# board.net
KiCad netlist of a schematic drawn in EAGLE
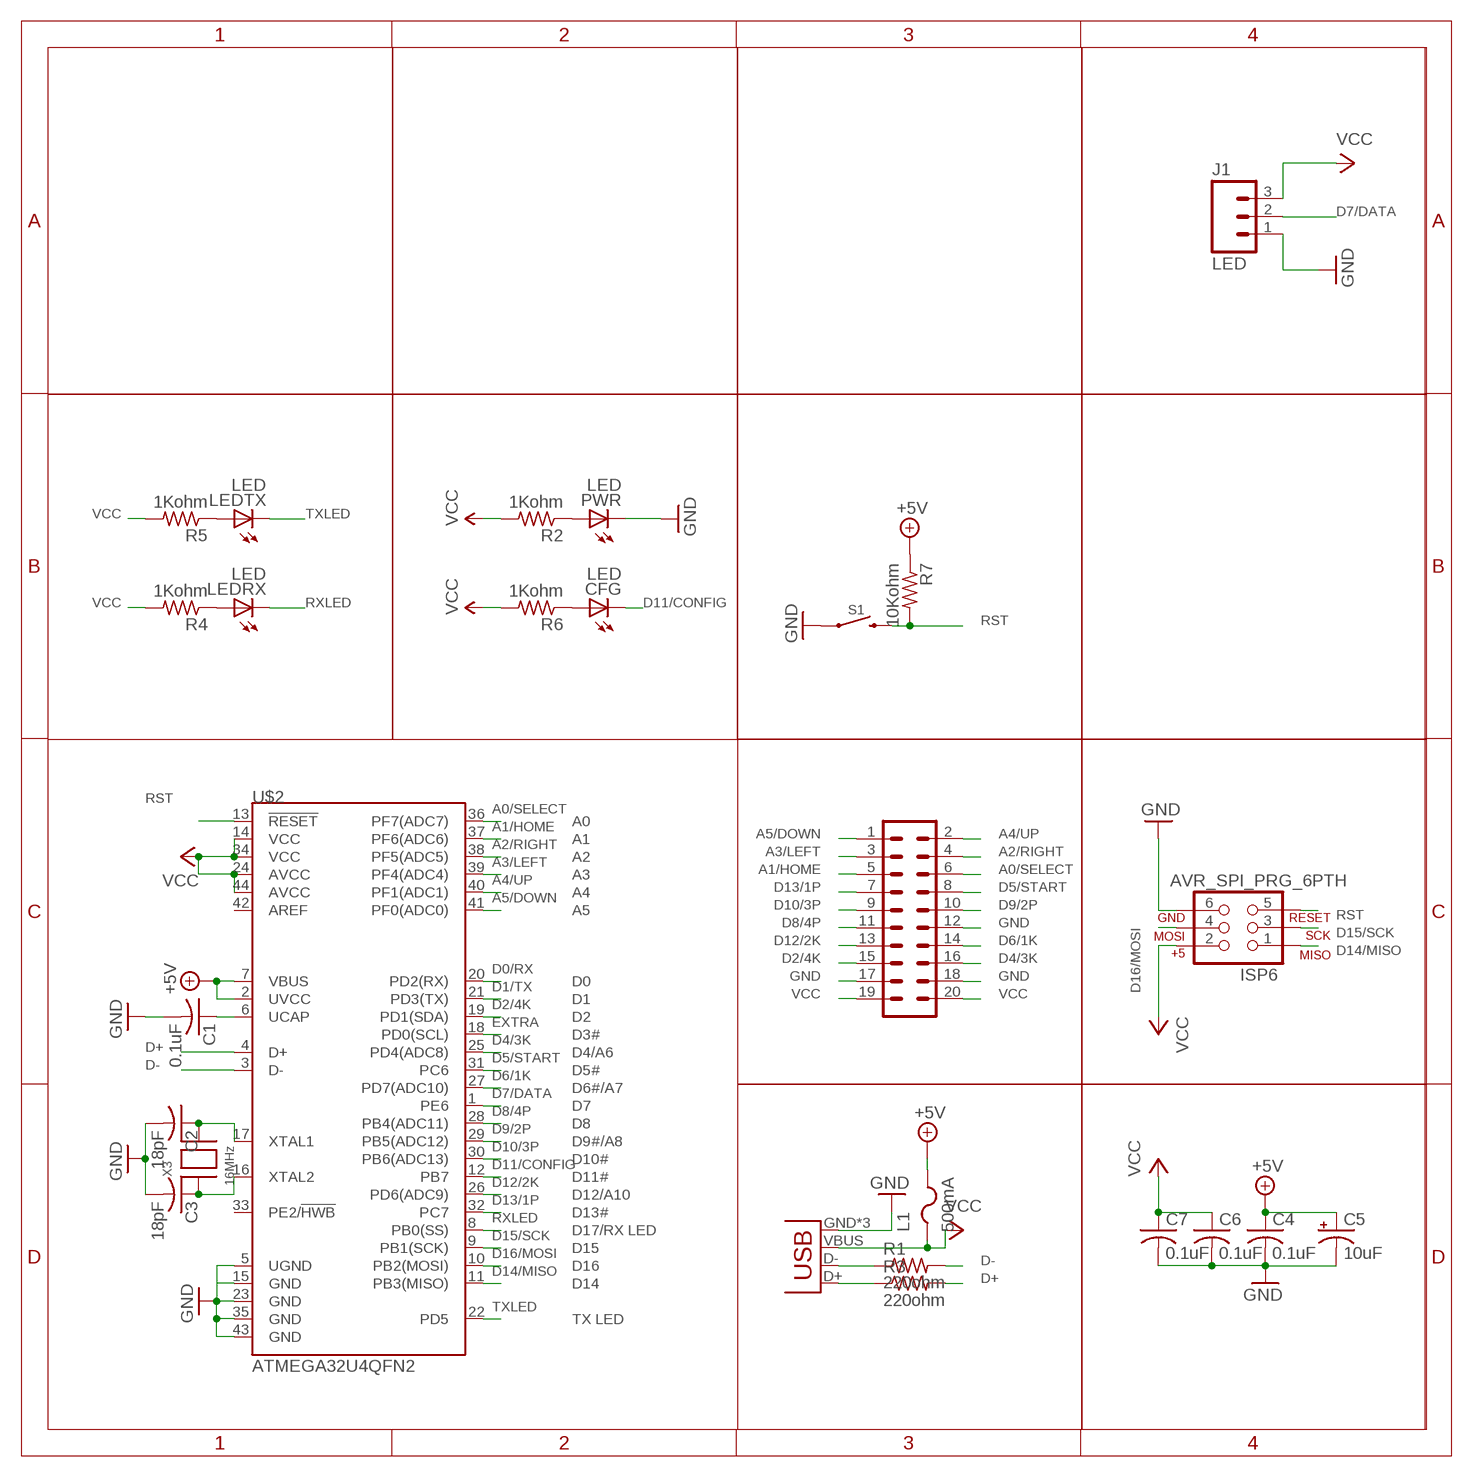
[diagram p0: schematic, sheet 1]

(export (version "E")
  (design (tool "Eeschema 10.0.6"))
  (components
    (comp (ref "C1")
      (value "0.1uF")
      (footprint "eagle-import:C0603")
      (libsource (lib "eagle-import") (part "C-USC0603"))
    )
    (comp (ref "C2")
      (value "18pF")
      (footprint "eagle-import:C0603")
      (libsource (lib "eagle-import") (part "C-USC0603"))
    )
    (comp (ref "C3")
      (value "18pF")
      (footprint "eagle-import:C0603")
      (libsource (lib "eagle-import") (part "C-USC0603"))
    )
    (comp (ref "C4")
      (value "0.1uF")
      (footprint "eagle-import:C0603")
      (libsource (lib "eagle-import") (part "C-USC0603"))
    )
    (comp (ref "C5")
      (value "10uF")
      (footprint "eagle-import:0603-POLAR")
      (libsource (lib "eagle-import") (part "10UF-POLAR-0603-6.3V-20%(TANT)"))
    )
    (comp (ref "C6")
      (value "0.1uF")
      (footprint "eagle-import:C0603")
      (libsource (lib "eagle-import") (part "C-USC0603"))
    )
    (comp (ref "C7")
      (value "0.1uF")
      (footprint "eagle-import:C0603")
      (libsource (lib "eagle-import") (part "C-USC0603"))
    )
    (comp (ref "CFG")
      (value "LED")
      (footprint "eagle-import:CHIPLED_0603")
      (libsource (lib "eagle-import") (part "LEDCHIPLED_0603"))
    )
    (comp (ref "CN1")
      (value "USB-MICROB")
      (footprint "eagle-import:USB-MICROB")
      (libsource (lib "eagle-import") (part "USB-MICROB"))
    )
    (comp (ref "ISP6")
      (value "AVR_SPI_PRG_6PTH")
      (footprint "eagle-import:2X3")
      (libsource (lib "eagle-import") (part "AVR_SPI_PRG_6PTH"))
    )
    (comp (ref "J1")
      (value "LED")
      (footprint "eagle-import:JST-3-PTH-VERT")
      (libsource (lib "eagle-import") (part "M03JST-PTH-VERT"))
    )
    (comp (ref "L1")
      (value "500mA")
      (footprint "eagle-import:R1206")
      (libsource (lib "eagle-import") (part "PTCFUSE-1206"))
    )
    (comp (ref "LEDRX")
      (value "LED")
      (footprint "eagle-import:CHIPLED_0603")
      (libsource (lib "eagle-import") (part "LEDCHIPLED_0603"))
    )
    (comp (ref "LEDTX")
      (value "LED")
      (footprint "eagle-import:CHIPLED_0603")
      (libsource (lib "eagle-import") (part "LEDCHIPLED_0603"))
    )
    (comp (ref "PWR")
      (value "LED")
      (footprint "eagle-import:CHIPLED_0603")
      (libsource (lib "eagle-import") (part "LEDCHIPLED_0603"))
    )
    (comp (ref "R1")
      (value "220ohm")
      (footprint "eagle-import:R0603")
      (libsource (lib "eagle-import") (part "R-US_R0603"))
    )
    (comp (ref "R2")
      (value "1Kohm")
      (footprint "eagle-import:R0603")
      (libsource (lib "eagle-import") (part "R-US_R0603"))
    )
    (comp (ref "R3")
      (value "220ohm")
      (footprint "eagle-import:R0603")
      (libsource (lib "eagle-import") (part "R-US_R0603"))
    )
    (comp (ref "R4")
      (value "1Kohm")
      (footprint "eagle-import:R0603")
      (libsource (lib "eagle-import") (part "R-US_R0603"))
    )
    (comp (ref "R5")
      (value "1Kohm")
      (footprint "eagle-import:R0603")
      (libsource (lib "eagle-import") (part "R-US_R0603"))
    )
    (comp (ref "R6")
      (value "1Kohm")
      (footprint "eagle-import:R0603")
      (libsource (lib "eagle-import") (part "R-US_R0603"))
    )
    (comp (ref "R7")
      (value "10Kohm")
      (footprint "eagle-import:R0603")
      (libsource (lib "eagle-import") (part "R-US_R0603"))
    )
    (comp (ref "S1")
      (value "MOMENTARY-SWITCH-SPST-SMD-4.6X2.8MM")
      (footprint "eagle-import:TACTILE_SWITCH_SMD_4.6X2.8MM")
      (libsource (lib "eagle-import") (part "MOMENTARY-SWITCH-SPST-SMD-4.6X2.8MM"))
    )
    (comp (ref "U$1")
      (value "M10X2")
      (footprint "eagle-import:2X10")
      (libsource (lib "eagle-import") (part "M10X2"))
    )
    (comp (ref "U$2")
      (value "ATMEGA32U4QFN2")
      (footprint "eagle-import:SPARKFUN-DIGITALIC_QFN-44-NOPAD")
      (libsource (lib "eagle-import") (part "ATMEGA32U4QFN2"))
    )
    (comp (ref "X3")
      (value "16MHz")
      (footprint "eagle-import:NX5032")
      (libsource (lib "eagle-import") (part "XTALNX5032"))
    )
  )
  (nets
    (net (code "1") (name "+5V") (class "Default")
      (node (ref "C4") (pin "1") (pinfunction "1_1") (pintype "passive"))
      (node (ref "C5") (pin "+") (pinfunction "+_+") (pintype "passive"))
      (node (ref "L1") (pin "2") (pinfunction "2_2") (pintype "passive"))
      (node (ref "R7") (pin "1") (pinfunction "1_1") (pintype "passive"))
      (node (ref "U$2") (pin "2") (pinfunction "UVCC_2") (pintype "bidirectional"))
      (node (ref "U$2") (pin "7") (pinfunction "VBUS_7") (pintype "bidirectional"))
    )
    (net (code "2") (name "/A0{slash}SELECT") (class "Default")
      (node (ref "U$1") (pin "6") (pinfunction "6_6") (pintype "passive"))
      (node (ref "U$2") (pin "36") (pinfunction "PF7(ADC7)_36") (pintype "bidirectional"))
    )
    (net (code "3") (name "/A1{slash}HOME") (class "Default")
      (node (ref "U$1") (pin "5") (pinfunction "5_5") (pintype "passive"))
      (node (ref "U$2") (pin "37") (pinfunction "PF6(ADC6)_37") (pintype "bidirectional"))
    )
    (net (code "4") (name "/A2{slash}RIGHT") (class "Default")
      (node (ref "U$1") (pin "4") (pinfunction "4_4") (pintype "passive"))
      (node (ref "U$2") (pin "38") (pinfunction "PF5(ADC5)_38") (pintype "bidirectional"))
    )
    (net (code "5") (name "/A3{slash}LEFT") (class "Default")
      (node (ref "U$1") (pin "3") (pinfunction "3_3") (pintype "passive"))
      (node (ref "U$2") (pin "39") (pinfunction "PF4(ADC4)_39") (pintype "bidirectional"))
    )
    (net (code "6") (name "/A4{slash}UP") (class "Default")
      (node (ref "U$1") (pin "2") (pinfunction "2_2") (pintype "passive"))
      (node (ref "U$2") (pin "40") (pinfunction "PF1(ADC1)_40") (pintype "bidirectional"))
    )
    (net (code "7") (name "/A5{slash}DOWN") (class "Default")
      (node (ref "U$1") (pin "1") (pinfunction "1_1") (pintype "passive"))
      (node (ref "U$2") (pin "41") (pinfunction "PF0(ADC0)_41") (pintype "bidirectional"))
    )
    (net (code "8") (name "/D+") (class "Default")
      (node (ref "R3") (pin "2") (pinfunction "2_2") (pintype "passive"))
      (node (ref "U$2") (pin "4") (pinfunction "D+_4") (pintype "bidirectional"))
    )
    (net (code "9") (name "/D-") (class "Default")
      (node (ref "R1") (pin "2") (pinfunction "2_2") (pintype "passive"))
      (node (ref "U$2") (pin "3") (pinfunction "D-_3") (pintype "bidirectional"))
    )
    (net (code "10") (name "/D0{slash}RX") (class "Default")
      (node (ref "U$2") (pin "20") (pinfunction "PD2(RX)_20") (pintype "bidirectional"))
    )
    (net (code "11") (name "/D1{slash}TX") (class "Default")
      (node (ref "U$2") (pin "21") (pinfunction "PD3(TX)_21") (pintype "bidirectional"))
    )
    (net (code "12") (name "/D2{slash}4K") (class "Default")
      (node (ref "U$1") (pin "15") (pinfunction "15_15") (pintype "passive"))
      (node (ref "U$2") (pin "19") (pinfunction "PD1(SDA)_19") (pintype "bidirectional"))
    )
    (net (code "13") (name "/D4{slash}3K") (class "Default")
      (node (ref "U$1") (pin "16") (pinfunction "16_16") (pintype "passive"))
      (node (ref "U$2") (pin "25") (pinfunction "PD4(ADC8)_25") (pintype "bidirectional"))
    )
    (net (code "14") (name "/D5{slash}START") (class "Default")
      (node (ref "U$1") (pin "8") (pinfunction "8_8") (pintype "passive"))
      (node (ref "U$2") (pin "31") (pinfunction "PC6_31") (pintype "bidirectional"))
    )
    (net (code "15") (name "/D6{slash}1K") (class "Default")
      (node (ref "U$1") (pin "14") (pinfunction "14_14") (pintype "passive"))
      (node (ref "U$2") (pin "27") (pinfunction "PD7(ADC10)_27") (pintype "bidirectional"))
    )
    (net (code "16") (name "/D7{slash}DATA") (class "Default")
      (node (ref "J1") (pin "2") (pinfunction "2_2") (pintype "passive"))
      (node (ref "U$2") (pin "1") (pinfunction "PE6_1") (pintype "bidirectional"))
    )
    (net (code "17") (name "/D8{slash}4P") (class "Default")
      (node (ref "U$1") (pin "11") (pinfunction "11_11") (pintype "passive"))
      (node (ref "U$2") (pin "28") (pinfunction "PB4(ADC11)_28") (pintype "bidirectional"))
    )
    (net (code "18") (name "/D9{slash}2P") (class "Default")
      (node (ref "U$1") (pin "10") (pinfunction "10_10") (pintype "passive"))
      (node (ref "U$2") (pin "29") (pinfunction "PB5(ADC12)_29") (pintype "bidirectional"))
    )
    (net (code "19") (name "/D10{slash}3P") (class "Default")
      (node (ref "U$1") (pin "9") (pinfunction "9_9") (pintype "passive"))
      (node (ref "U$2") (pin "30") (pinfunction "PB6(ADC13)_30") (pintype "bidirectional"))
    )
    (net (code "20") (name "/D11{slash}CONFIG") (class "Default")
      (node (ref "CFG") (pin "C") (pinfunction "C_C") (pintype "passive"))
      (node (ref "U$2") (pin "12") (pinfunction "PB7_12") (pintype "bidirectional"))
    )
    (net (code "21") (name "/D12{slash}2K") (class "Default")
      (node (ref "U$1") (pin "13") (pinfunction "13_13") (pintype "passive"))
      (node (ref "U$2") (pin "26") (pinfunction "PD6(ADC9)_26") (pintype "bidirectional"))
    )
    (net (code "22") (name "/D13{slash}1P") (class "Default")
      (node (ref "U$1") (pin "7") (pinfunction "7_7") (pintype "passive"))
      (node (ref "U$2") (pin "32") (pinfunction "PC7_32") (pintype "bidirectional"))
    )
    (net (code "23") (name "/D14{slash}MISO") (class "Default")
      (node (ref "ISP6") (pin "1") (pinfunction "1_1") (pintype "passive"))
      (node (ref "U$2") (pin "11") (pinfunction "PB3(MISO)_11") (pintype "bidirectional"))
    )
    (net (code "24") (name "/D15{slash}SCK") (class "Default")
      (node (ref "ISP6") (pin "3") (pinfunction "3_3") (pintype "passive"))
      (node (ref "U$2") (pin "9") (pinfunction "PB1(SCK)_9") (pintype "bidirectional"))
    )
    (net (code "25") (name "/D16{slash}MOSI") (class "Default")
      (node (ref "ISP6") (pin "4") (pinfunction "4_4") (pintype "passive"))
      (node (ref "U$2") (pin "10") (pinfunction "PB2(MOSI)_10") (pintype "bidirectional"))
    )
    (net (code "26") (name "/EXTRA") (class "Default")
      (node (ref "U$2") (pin "18") (pinfunction "PD0(SCL)_18") (pintype "bidirectional"))
    )
    (net (code "27") (name "/RST") (class "Default")
      (node (ref "ISP6") (pin "5") (pinfunction "5_5") (pintype "passive"))
      (node (ref "R7") (pin "2") (pinfunction "2_2") (pintype "passive"))
      (node (ref "S1") (pin "3") (pinfunction "2_3") (pintype "passive"))
      (node (ref "S1") (pin "4") (pinfunction "2_4") (pintype "passive"))
      (node (ref "U$2") (pin "13") (pinfunction "~{RESET}_13") (pintype "bidirectional"))
    )
    (net (code "28") (name "/RXLED") (class "Default")
      (node (ref "LEDRX") (pin "C") (pinfunction "C_C") (pintype "passive"))
      (node (ref "U$2") (pin "8") (pinfunction "PB0(SS)_8") (pintype "bidirectional"))
    )
    (net (code "29") (name "/TXLED") (class "Default")
      (node (ref "LEDTX") (pin "C") (pinfunction "C_C") (pintype "passive"))
      (node (ref "U$2") (pin "22") (pinfunction "PD5_22") (pintype "bidirectional"))
    )
    (net (code "30") (name "GND") (class "Default")
      (node (ref "C1") (pin "2") (pinfunction "2_2") (pintype "passive"))
      (node (ref "C2") (pin "2") (pinfunction "2_2") (pintype "passive"))
      (node (ref "C3") (pin "2") (pinfunction "2_2") (pintype "passive"))
      (node (ref "C4") (pin "2") (pinfunction "2_2") (pintype "passive"))
      (node (ref "C5") (pin "-") (pinfunction "-_-") (pintype "passive"))
      (node (ref "C6") (pin "2") (pinfunction "2_2") (pintype "passive"))
      (node (ref "C7") (pin "2") (pinfunction "2_2") (pintype "passive"))
      (node (ref "CN1") (pin "GND") (pinfunction "GND_GND") (pintype "bidirectional"))
      (node (ref "CN1") (pin "MT1") (pinfunction "GND_MT1") (pintype "bidirectional"))
      (node (ref "CN1") (pin "MT2") (pinfunction "GND_MT2") (pintype "bidirectional"))
      (node (ref "ISP6") (pin "6") (pinfunction "6_6") (pintype "passive"))
      (node (ref "J1") (pin "1") (pinfunction "1_1") (pintype "passive"))
      (node (ref "PWR") (pin "C") (pinfunction "C_C") (pintype "passive"))
      (node (ref "S1") (pin "1") (pinfunction "1_1") (pintype "passive"))
      (node (ref "S1") (pin "2") (pinfunction "1_2") (pintype "passive"))
      (node (ref "U$1") (pin "12") (pinfunction "12_12") (pintype "passive"))
      (node (ref "U$1") (pin "17") (pinfunction "17_17") (pintype "passive"))
      (node (ref "U$1") (pin "18") (pinfunction "18_18") (pintype "passive"))
      (node (ref "U$2") (pin "15") (pinfunction "GND_15") (pintype "bidirectional"))
      (node (ref "U$2") (pin "23") (pinfunction "GND_23") (pintype "bidirectional"))
      (node (ref "U$2") (pin "35") (pinfunction "GND_35") (pintype "bidirectional"))
      (node (ref "U$2") (pin "43") (pinfunction "GND_43") (pintype "bidirectional"))
      (node (ref "U$2") (pin "5") (pinfunction "UGND_5") (pintype "bidirectional"))
    )
    (net (code "31") (name "Net-(CFG-PadA)") (class "Default")
      (node (ref "CFG") (pin "A") (pinfunction "A_A") (pintype "passive"))
      (node (ref "R6") (pin "1") (pinfunction "1_1") (pintype "passive"))
    )
    (net (code "32") (name "Net-(CN1-PadD+)") (class "Default")
      (node (ref "CN1") (pin "D+") (pinfunction "D+_D+") (pintype "bidirectional"))
      (node (ref "R3") (pin "1") (pinfunction "1_1") (pintype "passive"))
    )
    (net (code "33") (name "Net-(CN1-PadD-)") (class "Default")
      (node (ref "CN1") (pin "D-") (pinfunction "D-_D-") (pintype "bidirectional"))
      (node (ref "R1") (pin "1") (pinfunction "1_1") (pintype "passive"))
    )
    (net (code "34") (name "Net-(LEDRX-PadA)") (class "Default")
      (node (ref "LEDRX") (pin "A") (pinfunction "A_A") (pintype "passive"))
      (node (ref "R4") (pin "1") (pinfunction "1_1") (pintype "passive"))
    )
    (net (code "35") (name "Net-(LEDTX-PadA)") (class "Default")
      (node (ref "LEDTX") (pin "A") (pinfunction "A_A") (pintype "passive"))
      (node (ref "R5") (pin "1") (pinfunction "1_1") (pintype "passive"))
    )
    (net (code "36") (name "Net-(PWR-PadA)") (class "Default")
      (node (ref "PWR") (pin "A") (pinfunction "A_A") (pintype "passive"))
      (node (ref "R2") (pin "1") (pinfunction "1_1") (pintype "passive"))
    )
    (net (code "37") (name "Net-(U$2-UCAP)") (class "Default")
      (node (ref "C1") (pin "1") (pinfunction "1_1") (pintype "passive"))
      (node (ref "U$2") (pin "6") (pinfunction "UCAP_6") (pintype "bidirectional"))
    )
    (net (code "38") (name "Net-(U$2-XTAL1)") (class "Default")
      (node (ref "C2") (pin "1") (pinfunction "1_1") (pintype "passive"))
      (node (ref "U$2") (pin "17") (pinfunction "XTAL1_17") (pintype "bidirectional"))
      (node (ref "X3") (pin "P$2") (pinfunction "P$2_P$2") (pintype "bidirectional"))
    )
    (net (code "39") (name "Net-(U$2-XTAL2)") (class "Default")
      (node (ref "C3") (pin "1") (pinfunction "1_1") (pintype "passive"))
      (node (ref "U$2") (pin "16") (pinfunction "XTAL2_16") (pintype "bidirectional"))
      (node (ref "X3") (pin "P$1") (pinfunction "P$1_P$1") (pintype "bidirectional"))
    )
    (net (code "40") (name "VCC") (class "Default")
      (node (ref "C6") (pin "1") (pinfunction "1_1") (pintype "passive"))
      (node (ref "C7") (pin "1") (pinfunction "1_1") (pintype "passive"))
      (node (ref "CN1") (pin "VBUS") (pinfunction "VBUS_VBUS") (pintype "bidirectional"))
      (node (ref "ISP6") (pin "2") (pinfunction "2_2") (pintype "passive"))
      (node (ref "J1") (pin "3") (pinfunction "3_3") (pintype "passive"))
      (node (ref "L1") (pin "1") (pinfunction "1_1") (pintype "passive"))
      (node (ref "R2") (pin "2") (pinfunction "2_2") (pintype "passive"))
      (node (ref "R4") (pin "2") (pinfunction "2_2") (pintype "passive"))
      (node (ref "R5") (pin "2") (pinfunction "2_2") (pintype "passive"))
      (node (ref "R6") (pin "2") (pinfunction "2_2") (pintype "passive"))
      (node (ref "U$1") (pin "19") (pinfunction "19_19") (pintype "passive"))
      (node (ref "U$1") (pin "20") (pinfunction "20_20") (pintype "passive"))
      (node (ref "U$2") (pin "14") (pinfunction "VCC_14") (pintype "bidirectional"))
      (node (ref "U$2") (pin "24") (pinfunction "AVCC_24") (pintype "bidirectional"))
      (node (ref "U$2") (pin "34") (pinfunction "VCC_34") (pintype "bidirectional"))
      (node (ref "U$2") (pin "44") (pinfunction "AVCC_44") (pintype "bidirectional"))
    )
    (net (code "41") (name "unconnected-(U$2-AREF-Pad42)") (class "Default")
      (node (ref "U$2") (pin "42") (pinfunction "AREF_42") (pintype "bidirectional"))
    )
    (net (code "42") (name "unconnected-(U$2-PE2{slash}~{HWB}-Pad33)") (class "Default")
      (node (ref "U$2") (pin "33") (pinfunction "PE2/~{HWB}_33") (pintype "bidirectional"))
    )
  )
)
